# MCUSetup.net
KiCad netlist of a schematic drawn in Altium Designer
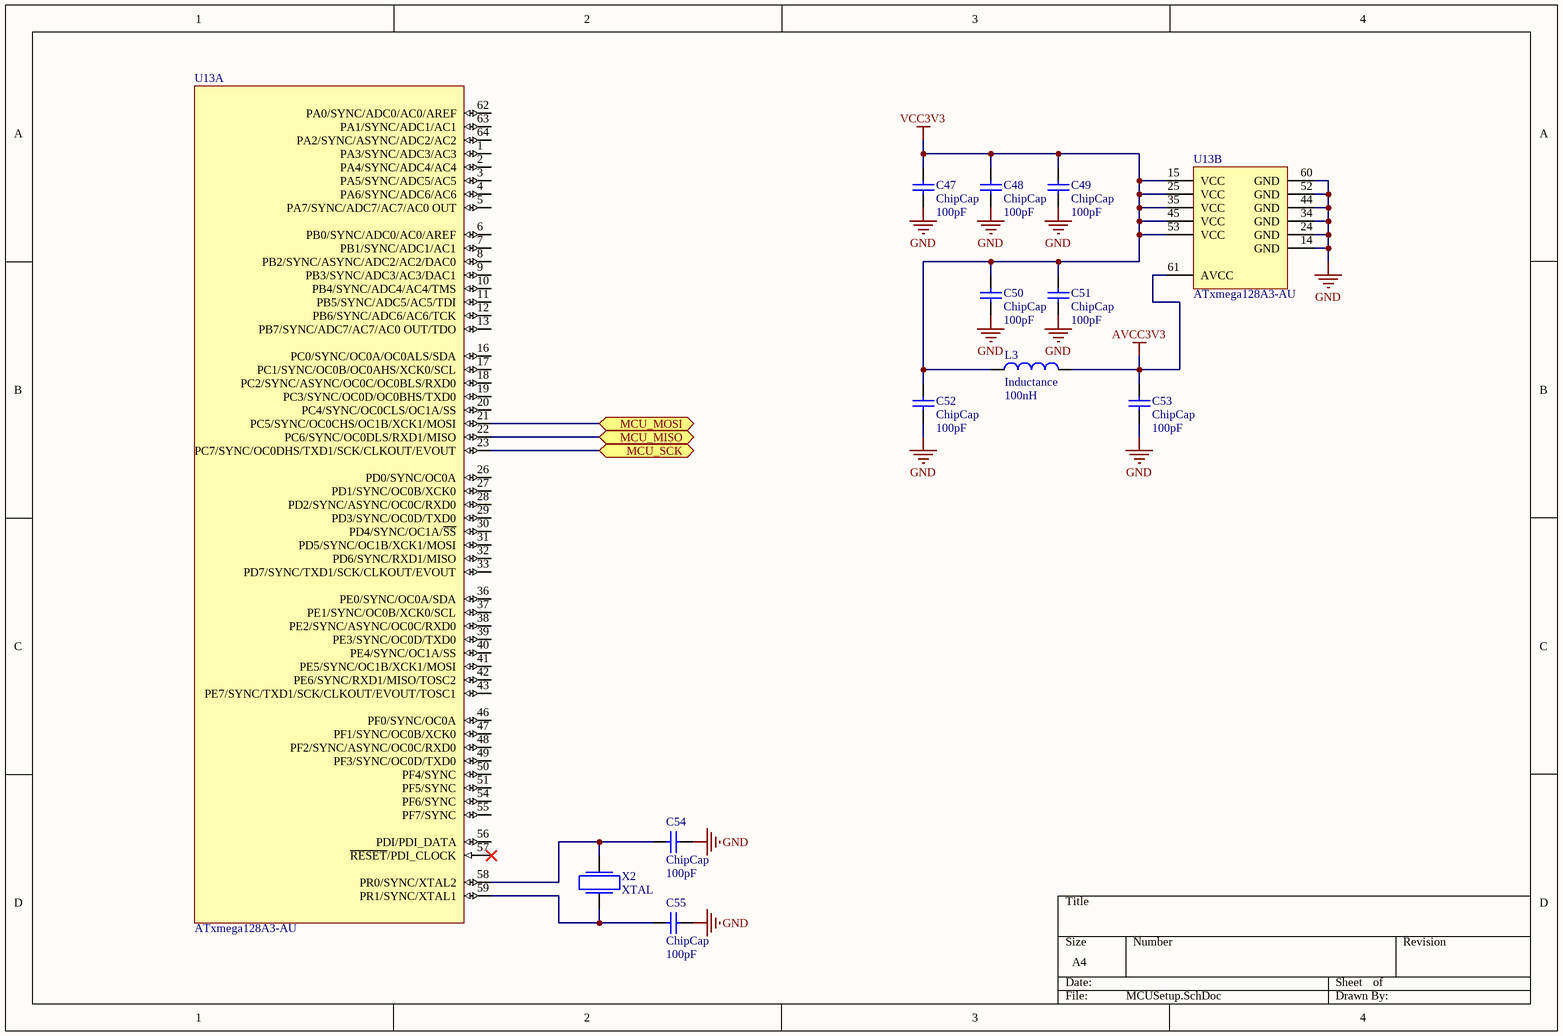
[diagram p0: MCUSetup.SchDoc]

(export (version "E")
  (design (tool "Eeschema 10.0.6"))
  (components
    (comp (ref "C47")
      (value "ChipCap")
      (footprint "CAP0805")
      (description "Capacitor")
      (fields (field (name "ALTIUM_VALUE") "100pF") (field (name "PUBLISHER") "Altium Limited"))
      (libsource (lib "Common Devices") (part "ChipCap"))
    )
    (comp (ref "C48")
      (value "ChipCap")
      (footprint "CAP0805")
      (description "Capacitor")
      (fields (field (name "ALTIUM_VALUE") "100pF") (field (name "PUBLISHER") "Altium Limited"))
      (libsource (lib "Common Devices") (part "ChipCap"))
    )
    (comp (ref "C49")
      (value "ChipCap")
      (footprint "CAP0805")
      (description "Capacitor")
      (fields (field (name "ALTIUM_VALUE") "100pF") (field (name "PUBLISHER") "Altium Limited"))
      (libsource (lib "Common Devices") (part "ChipCap"))
    )
    (comp (ref "C50")
      (value "ChipCap")
      (footprint "CAP0805")
      (description "Capacitor")
      (fields (field (name "ALTIUM_VALUE") "100pF") (field (name "PUBLISHER") "Altium Limited"))
      (libsource (lib "Common Devices") (part "ChipCap"))
    )
    (comp (ref "C51")
      (value "ChipCap")
      (footprint "CAP0805")
      (description "Capacitor")
      (fields (field (name "ALTIUM_VALUE") "100pF") (field (name "PUBLISHER") "Altium Limited"))
      (libsource (lib "Common Devices") (part "ChipCap"))
    )
    (comp (ref "C52")
      (value "ChipCap")
      (footprint "CAP0805")
      (description "Capacitor")
      (fields (field (name "ALTIUM_VALUE") "100pF") (field (name "PUBLISHER") "Altium Limited"))
      (libsource (lib "Common Devices") (part "ChipCap"))
    )
    (comp (ref "C53")
      (value "ChipCap")
      (footprint "CAP0805")
      (description "Capacitor")
      (fields (field (name "ALTIUM_VALUE") "100pF") (field (name "PUBLISHER") "Altium Limited"))
      (libsource (lib "Common Devices") (part "ChipCap"))
    )
    (comp (ref "C54")
      (value "ChipCap")
      (footprint "CAP0805")
      (description "Capacitor")
      (fields (field (name "ALTIUM_VALUE") "100pF") (field (name "PUBLISHER") "Altium Limited"))
      (libsource (lib "Common Devices") (part "ChipCap"))
    )
    (comp (ref "C55")
      (value "ChipCap")
      (footprint "CAP0805")
      (description "Capacitor")
      (fields (field (name "ALTIUM_VALUE") "100pF") (field (name "PUBLISHER") "Altium Limited"))
      (libsource (lib "Common Devices") (part "ChipCap"))
    )
    (comp (ref "L3")
      (value "Inductance")
      (footprint "CM45")
      (fields (field (name "ALTIUM_VALUE") "100nH"))
      (libsource (lib "Common Devices") (part "ChipInductance"))
    )
    (comp (ref "U13")
      (value "ATxmega128A3-AU")
      (footprint "64A_N")
      (fields (field (name "PUBLISHER") "Altium Limited"))
      (libsource (lib "Atmel Microcontroller 8-16-Bit AVR XMEGA") (part "ATxmega128A3-AU"))
    )
    (comp (ref "X2")
      (value "XTAL")
      (footprint "BCY-W2/E4.7")
      (description "Quartz crystall oscillator")
      (libsource (lib "Common Devices") (part "Crystall oscillator"))
    )
  )
  (nets
    (net (code "1") (name "/MCU_MISO") (class "Default")
      (node (ref "U13") (pin "22") (pinfunction "PC6/SYNC/OC0DLS/RXD1/MISO_22") (pintype "bidirectional"))
    )
    (net (code "2") (name "/MCU_MOSI") (class "Default")
      (node (ref "U13") (pin "21") (pinfunction "PC5/SYNC/OC0CHS/OC1B/XCK1/MOSI_21") (pintype "bidirectional"))
    )
    (net (code "3") (name "/MCU_SCK") (class "Default")
      (node (ref "U13") (pin "23") (pinfunction "PC7/SYNC/OC0DHS/TXD1/SCK/CLKOUT/EVOUT_23") (pintype "bidirectional"))
    )
    (net (code "4") (name "AVCC3V3") (class "Default")
      (node (ref "C53") (pin "2") (pinfunction "2_2") (pintype "passive"))
      (node (ref "L3") (pin "1") (pintype "passive"))
      (node (ref "U13") (pin "61") (pinfunction "AVCC_61") (pintype "power_in"))
    )
    (net (code "5") (name "GND") (class "Default")
      (node (ref "C47") (pin "1") (pinfunction "1_1") (pintype "passive"))
      (node (ref "C48") (pin "1") (pinfunction "1_1") (pintype "passive"))
      (node (ref "C49") (pin "1") (pinfunction "1_1") (pintype "passive"))
      (node (ref "C50") (pin "1") (pinfunction "1_1") (pintype "passive"))
      (node (ref "C51") (pin "1") (pinfunction "1_1") (pintype "passive"))
      (node (ref "C52") (pin "1") (pinfunction "1_1") (pintype "passive"))
      (node (ref "C53") (pin "1") (pinfunction "1_1") (pintype "passive"))
      (node (ref "C54") (pin "2") (pinfunction "2_2") (pintype "passive"))
      (node (ref "C55") (pin "2") (pinfunction "2_2") (pintype "passive"))
      (node (ref "U13") (pin "14") (pinfunction "GND_14") (pintype "power_in"))
      (node (ref "U13") (pin "24") (pinfunction "GND_24") (pintype "power_in"))
      (node (ref "U13") (pin "34") (pinfunction "GND_34") (pintype "power_in"))
      (node (ref "U13") (pin "44") (pinfunction "GND_44") (pintype "power_in"))
      (node (ref "U13") (pin "52") (pinfunction "GND_52") (pintype "power_in"))
      (node (ref "U13") (pin "60") (pinfunction "GND_60") (pintype "power_in"))
    )
    (net (code "6") (name "Net-(U13A-PR0{slash}SYNC{slash}XTAL2)") (class "Default")
      (node (ref "C54") (pin "1") (pinfunction "1_1") (pintype "passive"))
      (node (ref "U13") (pin "58") (pinfunction "PR0/SYNC/XTAL2_58") (pintype "bidirectional"))
      (node (ref "X2") (pin "2") (pinfunction "2_2") (pintype "passive"))
    )
    (net (code "7") (name "Net-(U13A-PR1{slash}SYNC{slash}XTAL1)") (class "Default")
      (node (ref "C55") (pin "1") (pinfunction "1_1") (pintype "passive"))
      (node (ref "U13") (pin "59") (pinfunction "PR1/SYNC/XTAL1_59") (pintype "bidirectional"))
      (node (ref "X2") (pin "1") (pinfunction "1_1") (pintype "passive"))
    )
    (net (code "8") (name "VCC3V3") (class "Default")
      (node (ref "C47") (pin "2") (pinfunction "2_2") (pintype "passive"))
      (node (ref "C48") (pin "2") (pinfunction "2_2") (pintype "passive"))
      (node (ref "C49") (pin "2") (pinfunction "2_2") (pintype "passive"))
      (node (ref "C50") (pin "2") (pinfunction "2_2") (pintype "passive"))
      (node (ref "C51") (pin "2") (pinfunction "2_2") (pintype "passive"))
      (node (ref "C52") (pin "2") (pinfunction "2_2") (pintype "passive"))
      (node (ref "L3") (pin "2") (pintype "passive"))
      (node (ref "U13") (pin "15") (pinfunction "VCC_15") (pintype "power_in"))
      (node (ref "U13") (pin "25") (pinfunction "VCC_25") (pintype "power_in"))
      (node (ref "U13") (pin "35") (pinfunction "VCC_35") (pintype "power_in"))
      (node (ref "U13") (pin "45") (pinfunction "VCC_45") (pintype "power_in"))
      (node (ref "U13") (pin "53") (pinfunction "VCC_53") (pintype "power_in"))
    )
    (net (code "9") (name "unconnected-(U13A-PA0{slash}SYNC{slash}ADC0{slash}AC0{slash}AREF-Pad62)") (class "Default")
      (node (ref "U13") (pin "62") (pinfunction "PA0/SYNC/ADC0/AC0/AREF_62") (pintype "bidirectional"))
    )
    (net (code "10") (name "unconnected-(U13A-PA1{slash}SYNC{slash}ADC1{slash}AC1-Pad63)") (class "Default")
      (node (ref "U13") (pin "63") (pinfunction "PA1/SYNC/ADC1/AC1_63") (pintype "bidirectional"))
    )
    (net (code "11") (name "unconnected-(U13A-PA2{slash}SYNC{slash}ASYNC{slash}ADC2{slash}AC2-Pad64)") (class "Default")
      (node (ref "U13") (pin "64") (pinfunction "PA2/SYNC/ASYNC/ADC2/AC2_64") (pintype "bidirectional"))
    )
    (net (code "12") (name "unconnected-(U13A-PA3{slash}SYNC{slash}ADC3{slash}AC3-Pad1)") (class "Default")
      (node (ref "U13") (pin "1") (pinfunction "PA3/SYNC/ADC3/AC3_1") (pintype "bidirectional"))
    )
    (net (code "13") (name "unconnected-(U13A-PA4{slash}SYNC{slash}ADC4{slash}AC4-Pad2)") (class "Default")
      (node (ref "U13") (pin "2") (pinfunction "PA4/SYNC/ADC4/AC4_2") (pintype "bidirectional"))
    )
    (net (code "14") (name "unconnected-(U13A-PA5{slash}SYNC{slash}ADC5{slash}AC5-Pad3)") (class "Default")
      (node (ref "U13") (pin "3") (pinfunction "PA5/SYNC/ADC5/AC5_3") (pintype "bidirectional"))
    )
    (net (code "15") (name "unconnected-(U13A-PA6{slash}SYNC{slash}ADC6{slash}AC6-Pad4)") (class "Default")
      (node (ref "U13") (pin "4") (pinfunction "PA6/SYNC/ADC6/AC6_4") (pintype "bidirectional"))
    )
    (net (code "16") (name "unconnected-(U13A-PA7{slash}SYNC{slash}ADC7{slash}AC7{slash}AC0_OUT-Pad5)") (class "Default")
      (node (ref "U13") (pin "5") (pinfunction "PA7/SYNC/ADC7/AC7/AC0_OUT_5") (pintype "bidirectional"))
    )
    (net (code "17") (name "unconnected-(U13A-PB0{slash}SYNC{slash}ADC0{slash}AC0{slash}AREF-Pad6)") (class "Default")
      (node (ref "U13") (pin "6") (pinfunction "PB0/SYNC/ADC0/AC0/AREF_6") (pintype "bidirectional"))
    )
    (net (code "18") (name "unconnected-(U13A-PB1{slash}SYNC{slash}ADC1{slash}AC1-Pad7)") (class "Default")
      (node (ref "U13") (pin "7") (pinfunction "PB1/SYNC/ADC1/AC1_7") (pintype "bidirectional"))
    )
    (net (code "19") (name "unconnected-(U13A-PB2{slash}SYNC{slash}ASYNC{slash}ADC2{slash}AC2{slash}DAC0-Pad8)") (class "Default")
      (node (ref "U13") (pin "8") (pinfunction "PB2/SYNC/ASYNC/ADC2/AC2/DAC0_8") (pintype "bidirectional"))
    )
    (net (code "20") (name "unconnected-(U13A-PB3{slash}SYNC{slash}ADC3{slash}AC3{slash}DAC1-Pad9)") (class "Default")
      (node (ref "U13") (pin "9") (pinfunction "PB3/SYNC/ADC3/AC3/DAC1_9") (pintype "bidirectional"))
    )
    (net (code "21") (name "unconnected-(U13A-PB4{slash}SYNC{slash}ADC4{slash}AC4{slash}TMS-Pad10)") (class "Default")
      (node (ref "U13") (pin "10") (pinfunction "PB4/SYNC/ADC4/AC4/TMS_10") (pintype "bidirectional"))
    )
    (net (code "22") (name "unconnected-(U13A-PB5{slash}SYNC{slash}ADC5{slash}AC5{slash}TDI-Pad11)") (class "Default")
      (node (ref "U13") (pin "11") (pinfunction "PB5/SYNC/ADC5/AC5/TDI_11") (pintype "bidirectional"))
    )
    (net (code "23") (name "unconnected-(U13A-PB6{slash}SYNC{slash}ADC6{slash}AC6{slash}TCK-Pad12)") (class "Default")
      (node (ref "U13") (pin "12") (pinfunction "PB6/SYNC/ADC6/AC6/TCK_12") (pintype "bidirectional"))
    )
    (net (code "24") (name "unconnected-(U13A-PB7{slash}SYNC{slash}ADC7{slash}AC7{slash}AC0_OUT{slash}TDO-Pad13)") (class "Default")
      (node (ref "U13") (pin "13") (pinfunction "PB7/SYNC/ADC7/AC7/AC0_OUT/TDO_13") (pintype "bidirectional"))
    )
    (net (code "25") (name "unconnected-(U13A-PC0{slash}SYNC{slash}OC0A{slash}OC0ALS{slash}SDA-Pad16)") (class "Default")
      (node (ref "U13") (pin "16") (pinfunction "PC0/SYNC/OC0A/OC0ALS/SDA_16") (pintype "bidirectional"))
    )
    (net (code "26") (name "unconnected-(U13A-PC1{slash}SYNC{slash}OC0B{slash}OC0AHS{slash}XCK0{slash}SCL-Pad17)") (class "Default")
      (node (ref "U13") (pin "17") (pinfunction "PC1/SYNC/OC0B/OC0AHS/XCK0/SCL_17") (pintype "bidirectional"))
    )
    (net (code "27") (name "unconnected-(U13A-PC2{slash}SYNC{slash}ASYNC{slash}OC0C{slash}OC0BLS{slash}RXD0-Pad18)") (class "Default")
      (node (ref "U13") (pin "18") (pinfunction "PC2/SYNC/ASYNC/OC0C/OC0BLS/RXD0_18") (pintype "bidirectional"))
    )
    (net (code "28") (name "unconnected-(U13A-PC3{slash}SYNC{slash}OC0D{slash}OC0BHS{slash}TXD0-Pad19)") (class "Default")
      (node (ref "U13") (pin "19") (pinfunction "PC3/SYNC/OC0D/OC0BHS/TXD0_19") (pintype "bidirectional"))
    )
    (net (code "29") (name "unconnected-(U13A-PC4{slash}SYNC{slash}OC0CLS{slash}OC1A{slash}SS-Pad20)") (class "Default")
      (node (ref "U13") (pin "20") (pinfunction "PC4/SYNC/OC0CLS/OC1A/SS_20") (pintype "bidirectional"))
    )
    (net (code "30") (name "unconnected-(U13A-PD0{slash}SYNC{slash}OC0A-Pad26)") (class "Default")
      (node (ref "U13") (pin "26") (pinfunction "PD0/SYNC/OC0A_26") (pintype "bidirectional"))
    )
    (net (code "31") (name "unconnected-(U13A-PD1{slash}SYNC{slash}OC0B{slash}XCK0-Pad27)") (class "Default")
      (node (ref "U13") (pin "27") (pinfunction "PD1/SYNC/OC0B/XCK0_27") (pintype "bidirectional"))
    )
    (net (code "32") (name "unconnected-(U13A-PD2{slash}SYNC{slash}ASYNC{slash}OC0C{slash}RXD0-Pad28)") (class "Default")
      (node (ref "U13") (pin "28") (pinfunction "PD2/SYNC/ASYNC/OC0C/RXD0_28") (pintype "bidirectional"))
    )
    (net (code "33") (name "unconnected-(U13A-PD3{slash}SYNC{slash}OC0D{slash}TXD0-Pad29)") (class "Default")
      (node (ref "U13") (pin "29") (pinfunction "PD3/SYNC/OC0D/TXD0_29") (pintype "bidirectional"))
    )
    (net (code "34") (name "unconnected-(U13A-PD4{slash}SYNC{slash}OC1A{slash}~{SS}-Pad30)") (class "Default")
      (node (ref "U13") (pin "30") (pinfunction "PD4/SYNC/OC1A/~{SS}_30") (pintype "bidirectional"))
    )
    (net (code "35") (name "unconnected-(U13A-PD5{slash}SYNC{slash}OC1B{slash}XCK1{slash}MOSI-Pad31)") (class "Default")
      (node (ref "U13") (pin "31") (pinfunction "PD5/SYNC/OC1B/XCK1/MOSI_31") (pintype "bidirectional"))
    )
    (net (code "36") (name "unconnected-(U13A-PD6{slash}SYNC{slash}RXD1{slash}MISO-Pad32)") (class "Default")
      (node (ref "U13") (pin "32") (pinfunction "PD6/SYNC/RXD1/MISO_32") (pintype "bidirectional"))
    )
    (net (code "37") (name "unconnected-(U13A-PD7{slash}SYNC{slash}TXD1{slash}SCK{slash}CLKOUT{slash}EVOUT-Pad33)") (class "Default")
      (node (ref "U13") (pin "33") (pinfunction "PD7/SYNC/TXD1/SCK/CLKOUT/EVOUT_33") (pintype "bidirectional"))
    )
    (net (code "38") (name "unconnected-(U13A-PDI{slash}PDI_DATA-Pad56)") (class "Default")
      (node (ref "U13") (pin "56") (pinfunction "PDI/PDI_DATA_56") (pintype "bidirectional"))
    )
    (net (code "39") (name "unconnected-(U13A-PE0{slash}SYNC{slash}OC0A{slash}SDA-Pad36)") (class "Default")
      (node (ref "U13") (pin "36") (pinfunction "PE0/SYNC/OC0A/SDA_36") (pintype "bidirectional"))
    )
    (net (code "40") (name "unconnected-(U13A-PE1{slash}SYNC{slash}OC0B{slash}XCK0{slash}SCL-Pad37)") (class "Default")
      (node (ref "U13") (pin "37") (pinfunction "PE1/SYNC/OC0B/XCK0/SCL_37") (pintype "bidirectional"))
    )
    (net (code "41") (name "unconnected-(U13A-PE2{slash}SYNC{slash}ASYNC{slash}OC0C{slash}RXD0-Pad38)") (class "Default")
      (node (ref "U13") (pin "38") (pinfunction "PE2/SYNC/ASYNC/OC0C/RXD0_38") (pintype "bidirectional"))
    )
    (net (code "42") (name "unconnected-(U13A-PE3{slash}SYNC{slash}OC0D{slash}TXD0-Pad39)") (class "Default")
      (node (ref "U13") (pin "39") (pinfunction "PE3/SYNC/OC0D/TXD0_39") (pintype "bidirectional"))
    )
    (net (code "43") (name "unconnected-(U13A-PE4{slash}SYNC{slash}OC1A{slash}SS-Pad40)") (class "Default")
      (node (ref "U13") (pin "40") (pinfunction "PE4/SYNC/OC1A/SS_40") (pintype "bidirectional"))
    )
    (net (code "44") (name "unconnected-(U13A-PE5{slash}SYNC{slash}OC1B{slash}XCK1{slash}MOSI-Pad41)") (class "Default")
      (node (ref "U13") (pin "41") (pinfunction "PE5/SYNC/OC1B/XCK1/MOSI_41") (pintype "bidirectional"))
    )
    (net (code "45") (name "unconnected-(U13A-PE6{slash}SYNC{slash}RXD1{slash}MISO{slash}TOSC2-Pad42)") (class "Default")
      (node (ref "U13") (pin "42") (pinfunction "PE6/SYNC/RXD1/MISO/TOSC2_42") (pintype "bidirectional"))
    )
    (net (code "46") (name "unconnected-(U13A-PE7{slash}SYNC{slash}TXD1{slash}SCK{slash}CLKOUT{slash}EVOUT{slash}TOSC1-Pad43)") (class "Default")
      (node (ref "U13") (pin "43") (pinfunction "PE7/SYNC/TXD1/SCK/CLKOUT/EVOUT/TOSC1_43") (pintype "bidirectional"))
    )
    (net (code "47") (name "unconnected-(U13A-PF0{slash}SYNC{slash}OC0A-Pad46)") (class "Default")
      (node (ref "U13") (pin "46") (pinfunction "PF0/SYNC/OC0A_46") (pintype "bidirectional"))
    )
    (net (code "48") (name "unconnected-(U13A-PF1{slash}SYNC{slash}OC0B{slash}XCK0-Pad47)") (class "Default")
      (node (ref "U13") (pin "47") (pinfunction "PF1/SYNC/OC0B/XCK0_47") (pintype "bidirectional"))
    )
    (net (code "49") (name "unconnected-(U13A-PF2{slash}SYNC{slash}ASYNC{slash}OC0C{slash}RXD0-Pad48)") (class "Default")
      (node (ref "U13") (pin "48") (pinfunction "PF2/SYNC/ASYNC/OC0C/RXD0_48") (pintype "bidirectional"))
    )
    (net (code "50") (name "unconnected-(U13A-PF3{slash}SYNC{slash}OC0D{slash}TXD0-Pad49)") (class "Default")
      (node (ref "U13") (pin "49") (pinfunction "PF3/SYNC/OC0D/TXD0_49") (pintype "bidirectional"))
    )
    (net (code "51") (name "unconnected-(U13A-PF4{slash}SYNC-Pad50)") (class "Default")
      (node (ref "U13") (pin "50") (pinfunction "PF4/SYNC_50") (pintype "bidirectional"))
    )
    (net (code "52") (name "unconnected-(U13A-PF5{slash}SYNC-Pad51)") (class "Default")
      (node (ref "U13") (pin "51") (pinfunction "PF5/SYNC_51") (pintype "bidirectional"))
    )
    (net (code "53") (name "unconnected-(U13A-PF6{slash}SYNC-Pad54)") (class "Default")
      (node (ref "U13") (pin "54") (pinfunction "PF6/SYNC_54") (pintype "bidirectional"))
    )
    (net (code "54") (name "unconnected-(U13A-PF7{slash}SYNC-Pad55)") (class "Default")
      (node (ref "U13") (pin "55") (pinfunction "PF7/SYNC_55") (pintype "bidirectional"))
    )
    (net (code "55") (name "unconnected-(U13A-~{RESET}{slash}PDI_CLOCK-Pad57)") (class "Default")
      (node (ref "U13") (pin "57") (pinfunction "~{RESET}/PDI_CLOCK_57") (pintype "input+no_connect"))
    )
  )
)
